# current_driver.net
KiCad netlist of a schematic drawn in EAGLE
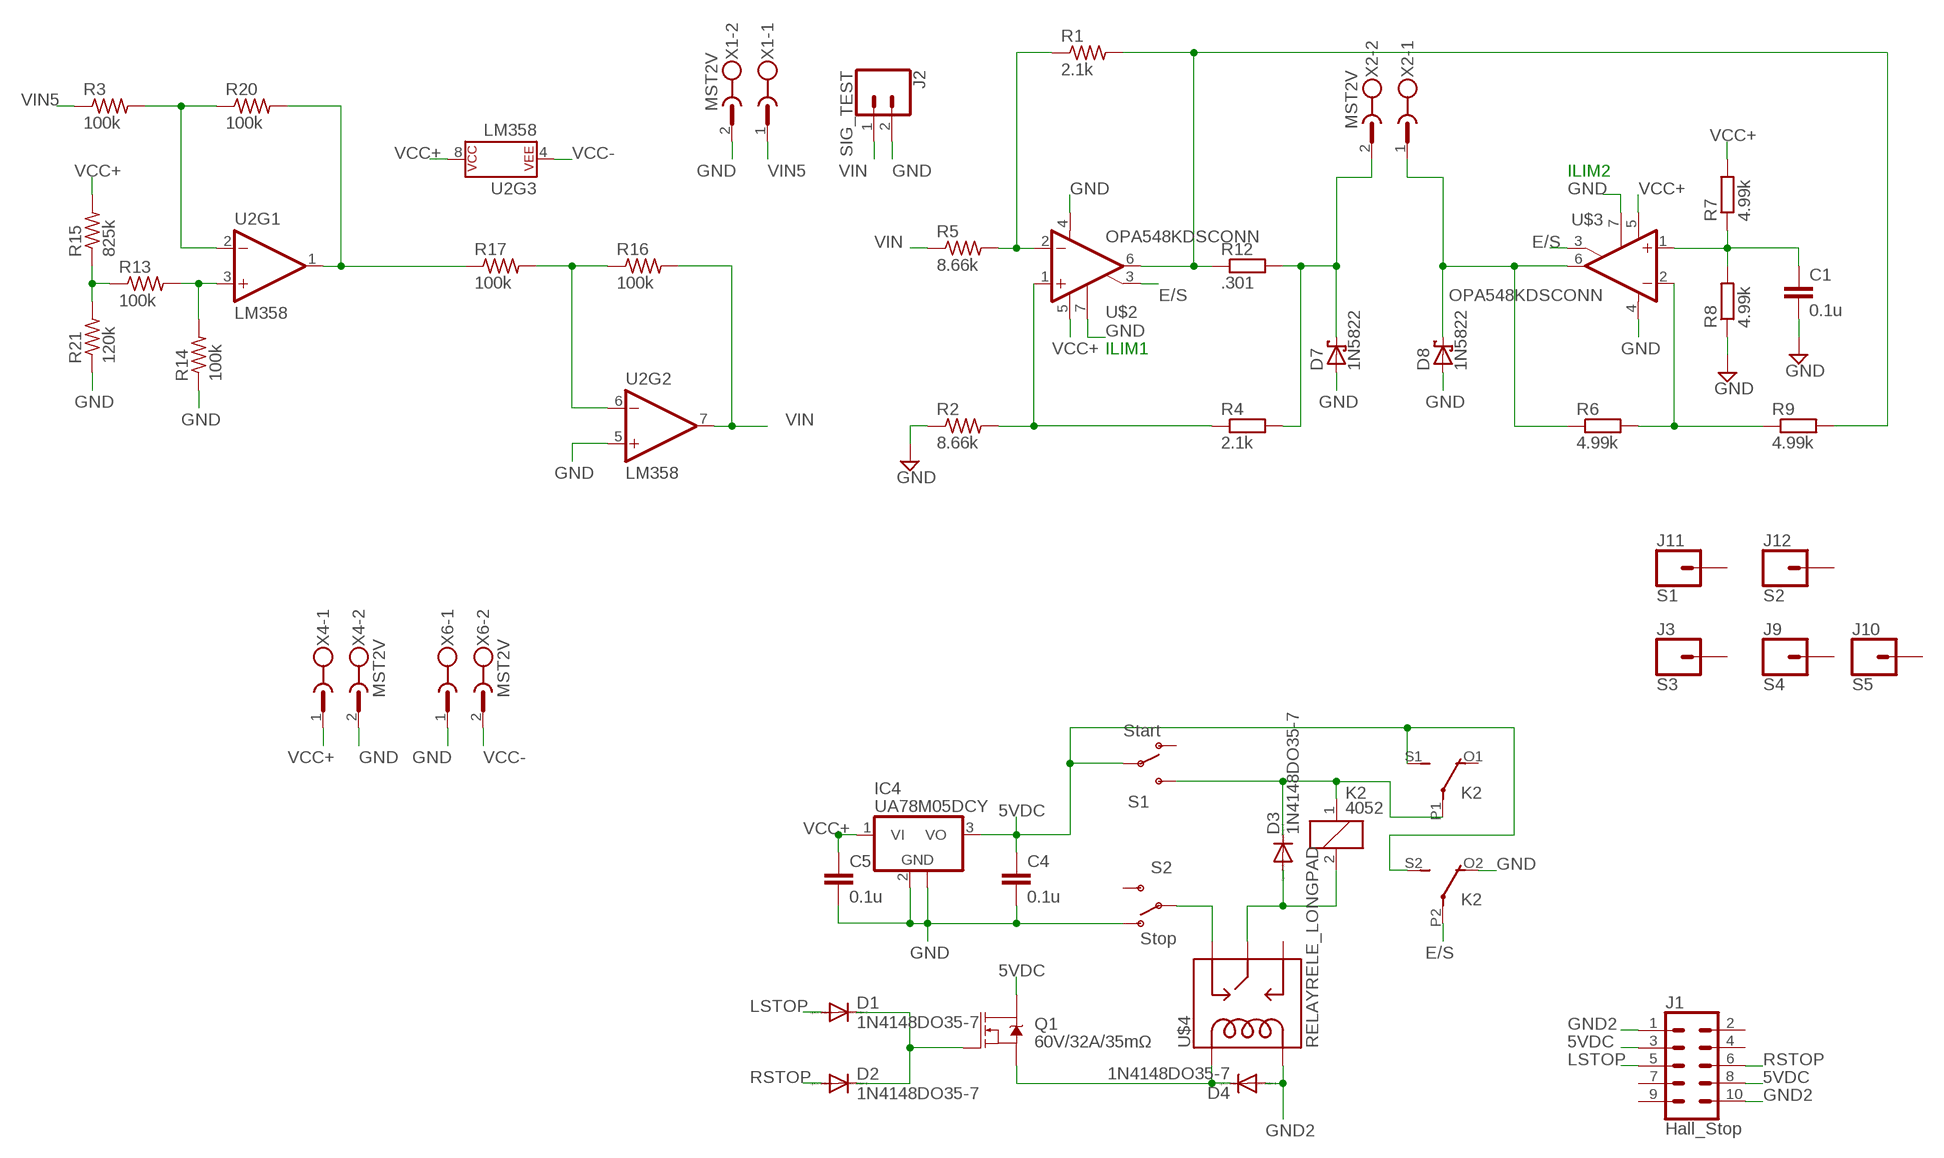
[diagram p0: schematic, sheet 1]

(export (version "E")
  (design (tool "Eeschema 10.0.6"))
  (components
    (comp (ref "C1")
      (value "0.1u")
      (footprint "eagle-import:C2012")
      (libsource (lib "eagle-import") (part "C-EUC2012"))
    )
    (comp (ref "C4")
      (value "0.1u")
      (footprint "eagle-import:C2012")
      (libsource (lib "eagle-import") (part "C-EUC2012"))
    )
    (comp (ref "C5")
      (value "0.1u")
      (footprint "eagle-import:C2012")
      (libsource (lib "eagle-import") (part "C-EUC2012"))
    )
    (comp (ref "D1")
      (value "1N4148DO35-7")
      (footprint "eagle-import:DO35-7")
      (libsource (lib "eagle-import") (part "1N4148DO35-7"))
    )
    (comp (ref "D2")
      (value "1N4148DO35-7")
      (footprint "eagle-import:DO35-7")
      (libsource (lib "eagle-import") (part "1N4148DO35-7"))
    )
    (comp (ref "D3")
      (value "1N4148DO35-7")
      (footprint "eagle-import:DO35-7")
      (libsource (lib "eagle-import") (part "1N4148DO35-7"))
    )
    (comp (ref "D4")
      (value "1N4148DO35-7")
      (footprint "eagle-import:DO35-7")
      (libsource (lib "eagle-import") (part "1N4148DO35-7"))
    )
    (comp (ref "D7")
      (value "1N5822")
      (footprint "eagle-import:F126Z12")
      (libsource (lib "eagle-import") (part "SCHOTTKY-DIODEF126Z12"))
    )
    (comp (ref "D8")
      (value "1N5822")
      (footprint "eagle-import:F126Z12")
      (libsource (lib "eagle-import") (part "SCHOTTKY-DIODEF126Z12"))
    )
    (comp (ref "IC4")
      (value "UA78M05DCY")
      (footprint "eagle-import:SOT223")
      (libsource (lib "eagle-import") (part "UA78MDCY05"))
    )
    (comp (ref "J1")
      (value "Hall_Stop")
      (footprint "eagle-import:2X5-SHROUDED_LOCK")
      (libsource (lib "eagle-import") (part "CONN_05X2SHD_LOCK"))
    )
    (comp (ref "J2")
      (value "SIG_TEST")
      (footprint "eagle-import:1X02_LOCK_LONGPADS")
      (libsource (lib "eagle-import") (part "CONN_02LOCK_LONGPADS"))
    )
    (comp (ref "J3")
      (value "S3")
      (footprint "eagle-import:1X01_LONGPAD")
      (libsource (lib "eagle-import") (part "CONN_01PTH_LONGPAD"))
    )
    (comp (ref "J9")
      (value "S4")
      (footprint "eagle-import:1X01_LONGPAD")
      (libsource (lib "eagle-import") (part "CONN_01PTH_LONGPAD"))
    )
    (comp (ref "J10")
      (value "S5")
      (footprint "eagle-import:1X01_LONGPAD")
      (libsource (lib "eagle-import") (part "CONN_01PTH_LONGPAD"))
    )
    (comp (ref "J11")
      (value "S1")
      (footprint "eagle-import:1X01_LONGPAD")
      (libsource (lib "eagle-import") (part "CONN_01PTH_LONGPAD"))
    )
    (comp (ref "J12")
      (value "S2")
      (footprint "eagle-import:1X01_LONGPAD")
      (libsource (lib "eagle-import") (part "CONN_01PTH_LONGPAD"))
    )
    (comp (ref "K2")
      (value "4052")
      (footprint "eagle-import:F4052")
      (libsource (lib "eagle-import") (part "4052"))
    )
    (comp (ref "Q1")
      (value "60V/32A/35mΩ")
      (footprint "eagle-import:TO220V")
      (libsource (lib "eagle-import") (part "MOSFET-NCH-FQP30N06L"))
    )
    (comp (ref "R1")
      (value "2.1k")
      (footprint "eagle-import:R0805")
      (libsource (lib "eagle-import") (part "R-US_R0805"))
    )
    (comp (ref "R2")
      (value "8.66k")
      (footprint "eagle-import:R0805")
      (libsource (lib "eagle-import") (part "R-US_R0805"))
    )
    (comp (ref "R3")
      (value "100k")
      (footprint "eagle-import:R0805")
      (libsource (lib "eagle-import") (part "R-US_R0805"))
    )
    (comp (ref "R4")
      (value "2.1k")
      (footprint "eagle-import:R0805")
      (libsource (lib "eagle-import") (part "resistor_R-EU_R0805"))
    )
    (comp (ref "R5")
      (value "8.66k")
      (footprint "eagle-import:R0805")
      (libsource (lib "eagle-import") (part "R-US_R0805"))
    )
    (comp (ref "R6")
      (value "4.99k")
      (footprint "eagle-import:R0805")
      (libsource (lib "eagle-import") (part "resistor_R-EU_R0805"))
    )
    (comp (ref "R7")
      (value "4.99k")
      (footprint "eagle-import:R0805")
      (libsource (lib "eagle-import") (part "resistor_R-EU_R0805"))
    )
    (comp (ref "R8")
      (value "4.99k")
      (footprint "eagle-import:R0805")
      (libsource (lib "eagle-import") (part "resistor_R-EU_R0805"))
    )
    (comp (ref "R9")
      (value "4.99k")
      (footprint "eagle-import:R0805")
      (libsource (lib "eagle-import") (part "resistor_R-EU_R0805"))
    )
    (comp (ref "R12")
      (value ".301")
      (footprint "eagle-import:M1206")
      (libsource (lib "eagle-import") (part "R-EU_M1206"))
    )
    (comp (ref "R13")
      (value "100k")
      (footprint "eagle-import:R0805")
      (libsource (lib "eagle-import") (part "R-US_R0805"))
    )
    (comp (ref "R14")
      (value "100k")
      (footprint "eagle-import:R0805")
      (libsource (lib "eagle-import") (part "R-US_R0805"))
    )
    (comp (ref "R15")
      (value "825k")
      (footprint "eagle-import:R0805")
      (libsource (lib "eagle-import") (part "R-US_R0805"))
    )
    (comp (ref "R16")
      (value "100k")
      (footprint "eagle-import:R0805")
      (libsource (lib "eagle-import") (part "R-US_R0805"))
    )
    (comp (ref "R17")
      (value "100k")
      (footprint "eagle-import:R0805")
      (libsource (lib "eagle-import") (part "R-US_R0805"))
    )
    (comp (ref "R20")
      (value "100k")
      (footprint "eagle-import:R0805")
      (libsource (lib "eagle-import") (part "R-US_R0805"))
    )
    (comp (ref "R21")
      (value "120k")
      (footprint "eagle-import:R0805")
      (libsource (lib "eagle-import") (part "R-US_R0805"))
    )
    (comp (ref "S1")
      (value "Start")
      (footprint "eagle-import:SWITCH_SPDT_SMD")
      (libsource (lib "eagle-import") (part "SWITCH-SPDTSMD"))
    )
    (comp (ref "S2")
      (value "Stop")
      (footprint "eagle-import:SWITCH_SPDT_SMD")
      (libsource (lib "eagle-import") (part "SWITCH-SPDTSMD"))
    )
    (comp (ref "U$2")
      (value "OPA548KDSCONN")
      (footprint "eagle-import:OPA548KDSCONN")
      (libsource (lib "eagle-import") (part "OPA548KDSCONN"))
    )
    (comp (ref "U$3")
      (value "OPA548KDSCONN")
      (footprint "eagle-import:OPA548KDSCONN")
      (libsource (lib "eagle-import") (part "OPA548KDSCONN"))
    )
    (comp (ref "U$4")
      (value "RELAYRELE_LONGPAD")
      (footprint "eagle-import:RELE_LONGPAD")
      (libsource (lib "eagle-import") (part "RELAYRELE_LONGPAD"))
    )
    (comp (ref "U2")
      (value "LM358")
      (footprint "eagle-import:DIP08_LONGPAD")
      (libsource (lib "eagle-import") (part "LM358DIP08_LONGPAD"))
    )
    (comp (ref "X1")
      (value "MST2V")
      (footprint "eagle-import:MSTBV2")
      (libsource (lib "eagle-import") (part "MST2V"))
    )
    (comp (ref "X2")
      (value "MST2V")
      (footprint "eagle-import:MSTBV2")
      (libsource (lib "eagle-import") (part "MST2V"))
    )
    (comp (ref "X4")
      (value "MST2V")
      (footprint "eagle-import:MSTBV2")
      (libsource (lib "eagle-import") (part "MST2V"))
    )
    (comp (ref "X6")
      (value "MST2V")
      (footprint "eagle-import:MSTBV2")
      (libsource (lib "eagle-import") (part "MST2V"))
    )
  )
  (nets
    (net (code "1") (name "/5VDC") (class "Default")
      (node (ref "C4") (pin "1") (pinfunction "1_1") (pintype "passive"))
      (node (ref "IC4") (pin "3") (pinfunction "VO_3") (pintype "passive"))
      (node (ref "J1") (pin "3") (pinfunction "3_3") (pintype "passive"))
      (node (ref "J1") (pin "8") (pinfunction "8_8") (pintype "passive"))
      (node (ref "K2") (pin "S1") (pinfunction "S_S1") (pintype "passive"))
      (node (ref "K2") (pin "S2") (pinfunction "S_S2") (pintype "passive"))
      (node (ref "Q1") (pin "2") (pinfunction "D_2") (pintype "bidirectional"))
      (node (ref "S1") (pin "2") (pinfunction "P_2") (pintype "passive"))
    )
    (net (code "2") (name "/E{slash}S") (class "Default")
      (node (ref "K2") (pin "P2") (pinfunction "P_P2") (pintype "passive"))
      (node (ref "U$2") (pin "3") (pinfunction "ILIM_3") (pintype "input"))
      (node (ref "U$3") (pin "3") (pinfunction "ILIM_3") (pintype "input"))
    )
    (net (code "3") (name "/GND2") (class "Default")
      (node (ref "D4") (pin "A") (pinfunction "A_A") (pintype "passive"))
      (node (ref "J1") (pin "1") (pinfunction "1_1") (pintype "passive"))
      (node (ref "J1") (pin "10") (pinfunction "10_10") (pintype "passive"))
      (node (ref "U$4") (pin "COIL0") (pinfunction "COIL0_COIL0") (pintype "bidirectional"))
    )
    (net (code "4") (name "/LSTOP") (class "Default")
      (node (ref "D1") (pin "A") (pinfunction "A_A") (pintype "passive"))
      (node (ref "J1") (pin "5") (pinfunction "5_5") (pintype "passive"))
    )
    (net (code "5") (name "/RSTOP") (class "Default")
      (node (ref "D2") (pin "A") (pinfunction "A_A") (pintype "passive"))
      (node (ref "J1") (pin "6") (pinfunction "6_6") (pintype "passive"))
    )
    (net (code "6") (name "/VCC+") (class "Default")
      (node (ref "C5") (pin "1") (pinfunction "1_1") (pintype "passive"))
      (node (ref "IC4") (pin "1") (pinfunction "VI_1") (pintype "input"))
      (node (ref "R15") (pin "2") (pinfunction "2_2") (pintype "passive"))
      (node (ref "R7") (pin "2") (pinfunction "2_2") (pintype "passive"))
      (node (ref "U$2") (pin "5") (pinfunction "V+_5") (pintype "power_in"))
      (node (ref "U$3") (pin "5") (pinfunction "V+_5") (pintype "power_in"))
      (node (ref "U2") (pin "8") (pinfunction "P$V+_8") (pintype "bidirectional"))
      (node (ref "X4") (pin "1") (pinfunction "1_1") (pintype "passive"))
    )
    (net (code "7") (name "/VCC-") (class "Default")
      (node (ref "U2") (pin "4") (pinfunction "P$V-_4") (pintype "bidirectional"))
      (node (ref "X6") (pin "2") (pinfunction "1_2") (pintype "passive"))
    )
    (net (code "8") (name "/VIN") (class "Default")
      (node (ref "J2") (pin "1") (pinfunction "1_1") (pintype "passive"))
      (node (ref "R16") (pin "2") (pinfunction "2_2") (pintype "passive"))
      (node (ref "R5") (pin "1") (pinfunction "1_1") (pintype "passive"))
      (node (ref "U2") (pin "7") (pinfunction "OUT_7") (pintype "output"))
    )
    (net (code "9") (name "/VIN5") (class "Default")
      (node (ref "R3") (pin "1") (pinfunction "1_1") (pintype "passive"))
      (node (ref "X1") (pin "1") (pinfunction "1_1") (pintype "passive"))
    )
    (net (code "10") (name "GND") (class "Default")
      (node (ref "C1") (pin "2") (pinfunction "2_2") (pintype "passive"))
      (node (ref "C4") (pin "2") (pinfunction "2_2") (pintype "passive"))
      (node (ref "C5") (pin "2") (pinfunction "2_2") (pintype "passive"))
      (node (ref "D7") (pin "A") (pinfunction "A_A") (pintype "passive"))
      (node (ref "D8") (pin "A") (pinfunction "A_A") (pintype "passive"))
      (node (ref "IC4") (pin "2") (pinfunction "GND_2") (pintype "passive"))
      (node (ref "IC4") (pin "4") (pinfunction "GND_4") (pintype "passive"))
      (node (ref "J2") (pin "2") (pinfunction "2_2") (pintype "passive"))
      (node (ref "K2") (pin "O2") (pinfunction "O_O2") (pintype "passive"))
      (node (ref "R14") (pin "1") (pinfunction "1_1") (pintype "passive"))
      (node (ref "R2") (pin "1") (pinfunction "1_1") (pintype "passive"))
      (node (ref "R21") (pin "1") (pinfunction "1_1") (pintype "passive"))
      (node (ref "R8") (pin "1") (pinfunction "1_1") (pintype "passive"))
      (node (ref "S2") (pin "1") (pinfunction "O_1") (pintype "passive"))
      (node (ref "U$2") (pin "4") (pinfunction "V-_4") (pintype "power_in"))
      (node (ref "U$2") (pin "7") (pinfunction "E/S_7") (pintype "bidirectional"))
      (node (ref "U$3") (pin "4") (pinfunction "V-_4") (pintype "power_in"))
      (node (ref "U$3") (pin "7") (pinfunction "E/S_7") (pintype "bidirectional"))
      (node (ref "U2") (pin "5") (pinfunction "+IN_5") (pintype "input"))
      (node (ref "X1") (pin "2") (pinfunction "1_2") (pintype "passive"))
      (node (ref "X4") (pin "2") (pinfunction "1_2") (pintype "passive"))
      (node (ref "X6") (pin "1") (pinfunction "1_1") (pintype "passive"))
    )
    (net (code "11") (name "Net-(D3-PadA)") (class "Default")
      (node (ref "D3") (pin "A") (pinfunction "A_A") (pintype "passive"))
      (node (ref "K2") (pin "2") (pinfunction "2_2") (pintype "passive"))
      (node (ref "U$4") (pin "SWCOMMON") (pinfunction "SWCOMMON_SWCOMMON") (pintype "bidirectional"))
    )
    (net (code "12") (name "Net-(K2B-P)") (class "Default")
      (node (ref "D3") (pin "C") (pinfunction "C_C") (pintype "passive"))
      (node (ref "K2") (pin "1") (pinfunction "1_1") (pintype "passive"))
      (node (ref "K2") (pin "P1") (pinfunction "P_P1") (pintype "passive"))
      (node (ref "S1") (pin "3") (pinfunction "S_3") (pintype "passive"))
    )
    (net (code "13") (name "Net-(Q1-G)") (class "Default")
      (node (ref "D1") (pin "C") (pinfunction "C_C") (pintype "passive"))
      (node (ref "D2") (pin "C") (pinfunction "C_C") (pintype "passive"))
      (node (ref "Q1") (pin "1") (pinfunction "G_1") (pintype "bidirectional"))
    )
    (net (code "14") (name "Net-(Q1-S)") (class "Default")
      (node (ref "D4") (pin "C") (pinfunction "C_C") (pintype "passive"))
      (node (ref "Q1") (pin "3") (pinfunction "S_3") (pintype "bidirectional"))
      (node (ref "U$4") (pin "COIL1") (pinfunction "COIL1_COIL1") (pintype "bidirectional"))
    )
    (net (code "15") (name "Net-(R13-Pad1)") (class "Default")
      (node (ref "R13") (pin "1") (pinfunction "1_1") (pintype "passive"))
      (node (ref "R15") (pin "1") (pinfunction "1_1") (pintype "passive"))
      (node (ref "R21") (pin "2") (pinfunction "2_2") (pintype "passive"))
    )
    (net (code "16") (name "Net-(S2-P)") (class "Default")
      (node (ref "S2") (pin "2") (pinfunction "P_2") (pintype "passive"))
      (node (ref "U$4") (pin "SWCLOSED") (pinfunction "SWCLOSE_SWCLOSED") (pintype "bidirectional"))
    )
    (net (code "17") (name "Net-(U$2-+IN)") (class "Default")
      (node (ref "R2") (pin "2") (pinfunction "2_2") (pintype "passive"))
      (node (ref "R4") (pin "1") (pinfunction "1_1") (pintype "passive"))
      (node (ref "U$2") (pin "1") (pinfunction "+IN_1") (pintype "input"))
    )
    (net (code "18") (name "Net-(U$2--IN)") (class "Default")
      (node (ref "R1") (pin "1") (pinfunction "1_1") (pintype "passive"))
      (node (ref "R5") (pin "2") (pinfunction "2_2") (pintype "passive"))
      (node (ref "U$2") (pin "2") (pinfunction "-IN_2") (pintype "input"))
    )
    (net (code "19") (name "Net-(U$2-OUT)") (class "Default")
      (node (ref "R1") (pin "2") (pinfunction "2_2") (pintype "passive"))
      (node (ref "R12") (pin "1") (pinfunction "1_1") (pintype "passive"))
      (node (ref "R9") (pin "2") (pinfunction "2_2") (pintype "passive"))
      (node (ref "U$2") (pin "6") (pinfunction "OUT_6") (pintype "output"))
    )
    (net (code "20") (name "Net-(U$3-+IN)") (class "Default")
      (node (ref "C1") (pin "1") (pinfunction "1_1") (pintype "passive"))
      (node (ref "R7") (pin "1") (pinfunction "1_1") (pintype "passive"))
      (node (ref "R8") (pin "2") (pinfunction "2_2") (pintype "passive"))
      (node (ref "U$3") (pin "1") (pinfunction "+IN_1") (pintype "input"))
    )
    (net (code "21") (name "Net-(U$3--IN)") (class "Default")
      (node (ref "R6") (pin "2") (pinfunction "2_2") (pintype "passive"))
      (node (ref "R9") (pin "1") (pinfunction "1_1") (pintype "passive"))
      (node (ref "U$3") (pin "2") (pinfunction "-IN_2") (pintype "input"))
    )
    (net (code "22") (name "Net-(U$3-OUT)") (class "Default")
      (node (ref "D8") (pin "C") (pinfunction "C_C") (pintype "passive"))
      (node (ref "R6") (pin "1") (pinfunction "1_1") (pintype "passive"))
      (node (ref "U$3") (pin "6") (pinfunction "OUT_6") (pintype "output"))
      (node (ref "X2") (pin "1") (pinfunction "1_1") (pintype "passive"))
    )
    (net (code "23") (name "Net-(U2A-+IN)") (class "Default")
      (node (ref "R13") (pin "2") (pinfunction "2_2") (pintype "passive"))
      (node (ref "R14") (pin "2") (pinfunction "2_2") (pintype "passive"))
      (node (ref "U2") (pin "3") (pinfunction "+IN_3") (pintype "input"))
    )
    (net (code "24") (name "Net-(U2A--IN)") (class "Default")
      (node (ref "R20") (pin "1") (pinfunction "1_1") (pintype "passive"))
      (node (ref "R3") (pin "2") (pinfunction "2_2") (pintype "passive"))
      (node (ref "U2") (pin "2") (pinfunction "-IN_2") (pintype "input"))
    )
    (net (code "25") (name "Net-(U2A-OUT)") (class "Default")
      (node (ref "R17") (pin "1") (pinfunction "1_1") (pintype "passive"))
      (node (ref "R20") (pin "2") (pinfunction "2_2") (pintype "passive"))
      (node (ref "U2") (pin "1") (pinfunction "OUT_1") (pintype "output"))
    )
    (net (code "26") (name "Net-(U2B--IN)") (class "Default")
      (node (ref "R16") (pin "1") (pinfunction "1_1") (pintype "passive"))
      (node (ref "R17") (pin "2") (pinfunction "2_2") (pintype "passive"))
      (node (ref "U2") (pin "6") (pinfunction "-IN_6") (pintype "input"))
    )
    (net (code "27") (name "Net-(X2B-1)") (class "Default")
      (node (ref "D7") (pin "C") (pinfunction "C_C") (pintype "passive"))
      (node (ref "R12") (pin "2") (pinfunction "2_2") (pintype "passive"))
      (node (ref "R4") (pin "2") (pinfunction "2_2") (pintype "passive"))
      (node (ref "X2") (pin "2") (pinfunction "1_2") (pintype "passive"))
    )
    (net (code "28") (name "unconnected-(J1-Pad2)") (class "Default")
      (node (ref "J1") (pin "2") (pinfunction "2_2") (pintype "passive"))
    )
    (net (code "29") (name "unconnected-(J1-Pad4)") (class "Default")
      (node (ref "J1") (pin "4") (pinfunction "4_4") (pintype "passive"))
    )
    (net (code "30") (name "unconnected-(J1-Pad7)") (class "Default")
      (node (ref "J1") (pin "7") (pinfunction "7_7") (pintype "passive"))
    )
    (net (code "31") (name "unconnected-(J1-Pad9)") (class "Default")
      (node (ref "J1") (pin "9") (pinfunction "9_9") (pintype "passive"))
    )
    (net (code "32") (name "unconnected-(J3-Pad1)") (class "Default")
      (node (ref "J3") (pin "1") (pinfunction "1_1") (pintype "passive"))
    )
    (net (code "33") (name "unconnected-(J9-Pad1)") (class "Default")
      (node (ref "J9") (pin "1") (pinfunction "1_1") (pintype "passive"))
    )
    (net (code "34") (name "unconnected-(J10-Pad1)") (class "Default")
      (node (ref "J10") (pin "1") (pinfunction "1_1") (pintype "passive"))
    )
    (net (code "35") (name "unconnected-(J11-Pad1)") (class "Default")
      (node (ref "J11") (pin "1") (pinfunction "1_1") (pintype "passive"))
    )
    (net (code "36") (name "unconnected-(J12-Pad1)") (class "Default")
      (node (ref "J12") (pin "1") (pinfunction "1_1") (pintype "passive"))
    )
    (net (code "37") (name "unconnected-(K2B-O-PadO1)") (class "Default")
      (node (ref "K2") (pin "O1") (pinfunction "O_O1") (pintype "passive"))
    )
    (net (code "38") (name "unconnected-(S1-O-Pad1)") (class "Default")
      (node (ref "S1") (pin "1") (pinfunction "O_1") (pintype "passive"))
    )
    (net (code "39") (name "unconnected-(S2-S-Pad3)") (class "Default")
      (node (ref "S2") (pin "3") (pinfunction "S_3") (pintype "passive"))
    )
    (net (code "40") (name "unconnected-(U$4-PadSWOPEN)") (class "Default")
      (node (ref "U$4") (pin "SWOPEN") (pinfunction "SWOPEN_SWOPEN") (pintype "bidirectional"))
    )
  )
)
